# Power_LDO_3V3.net
KiCad netlist of a schematic drawn in Altium Designer
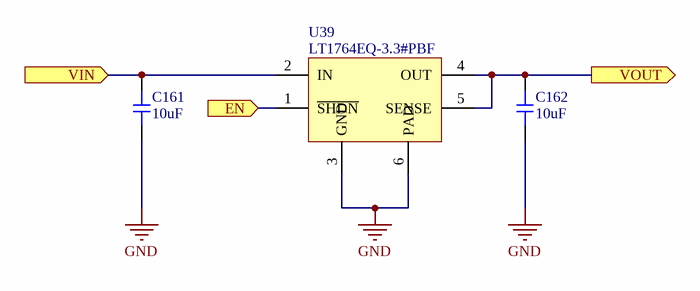
[diagram p0: Power_LDO_3V3.SchDoc]

(export (version "E")
  (design (tool "Eeschema 10.0.6"))
  (components
    (comp (ref "C161")
      (value "10uF")
      (footprint "0603-CAP")
      (description "Capacitor")
      (fields
        (field (name "MANUFACTURER") "Samsung")
        (field (name "MANUFACTURER PART NUMBER") "CL10A106KP8NNNC")
      )
      (libsource (lib "AMDC") (part "Capacitor"))
    )
    (comp (ref "C162")
      (value "10uF")
      (footprint "0603-CAP")
      (description "Capacitor")
      (fields
        (field (name "MANUFACTURER") "Samsung")
        (field (name "MANUFACTURER PART NUMBER") "CL10A106KP8NNNC")
      )
      (libsource (lib "AMDC") (part "Capacitor"))
    )
    (comp (ref "U39")
      (value "LT1764EQ-3.3#PBF")
      (footprint "5-DDPAK")
      (description "IC REG LINEAR 3.3V 3A 5DDPAK")
      (fields (field (name "MANUFACTURER") "Analog Devices / Linear Technology"))
      (libsource (lib "AMDC") (part "LT1764EQ-3.3#PBF"))
    )
  )
  (nets
    (net (code "1") (name "/EN") (class "Default")
      (node (ref "U39") (pin "1") (pinfunction "~{SHDN}_1") (pintype "passive"))
    )
    (net (code "2") (name "/VIN") (class "Default")
      (node (ref "C161") (pin "1") (pinfunction "1_1") (pintype "passive"))
      (node (ref "U39") (pin "2") (pinfunction "IN_2") (pintype "passive"))
    )
    (net (code "3") (name "/VOUT") (class "Default")
      (node (ref "C162") (pin "1") (pinfunction "1_1") (pintype "passive"))
      (node (ref "U39") (pin "4") (pinfunction "OUT_4") (pintype "passive"))
      (node (ref "U39") (pin "5") (pinfunction "SENSE_5") (pintype "passive"))
    )
    (net (code "4") (name "GND") (class "Default")
      (node (ref "C161") (pin "2") (pinfunction "2_2") (pintype "passive"))
      (node (ref "C162") (pin "2") (pinfunction "2_2") (pintype "passive"))
      (node (ref "U39") (pin "3") (pinfunction "GND_3") (pintype "passive"))
      (node (ref "U39") (pin "6") (pinfunction "PAD_6") (pintype "passive"))
    )
  )
)
